# CameraMux4.net
KiCad netlist of a schematic drawn in EAGLE
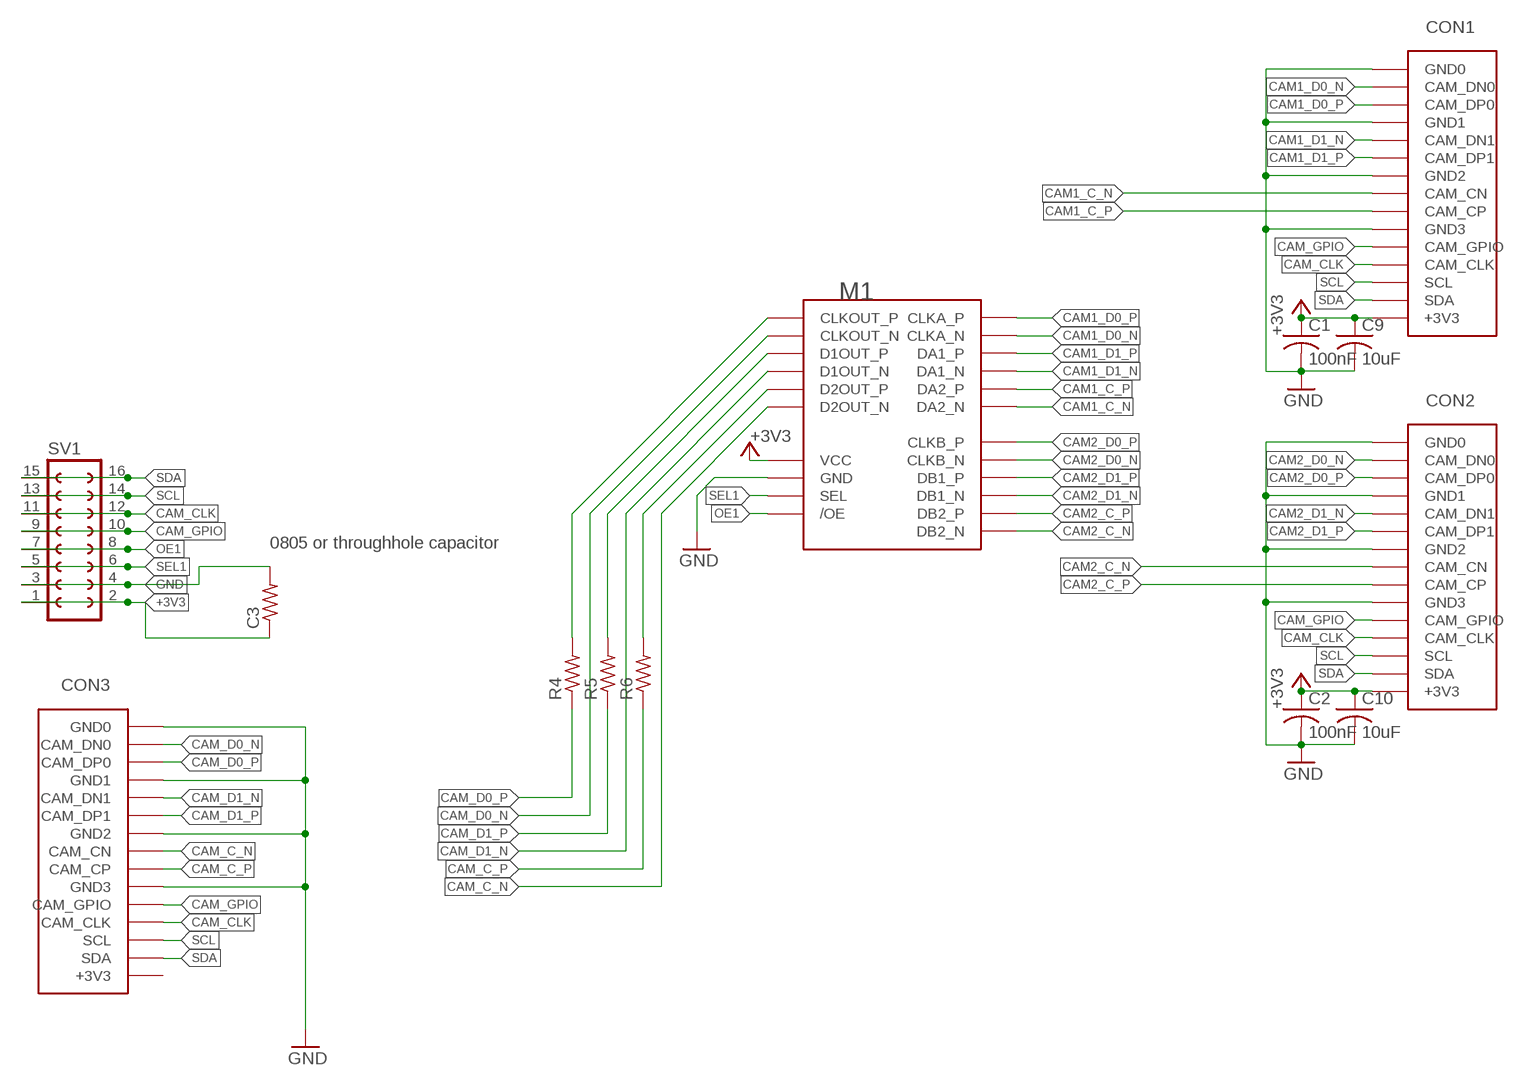
[diagram p0: schematic, sheet 1]

(export (version "E")
  (design (tool "Eeschema 10.0.6"))
  (components
    (comp (ref "C1")
      (value "100nF")
      (footprint "eagle-import:C0603")
      (libsource (lib "eagle-import") (part "C-USC0603"))
    )
    (comp (ref "C2")
      (value "100nF")
      (footprint "eagle-import:C0603")
      (libsource (lib "eagle-import") (part "C-USC0603"))
    )
    (comp (ref "C3")
      (value "R-US_FLIPFLOP")
      (footprint "eagle-import:0805-THM")
      (libsource (lib "eagle-import") (part "R-US_FLIPFLOP"))
    )
    (comp (ref "C9")
      (value "10uF")
      (footprint "eagle-import:C0603")
      (libsource (lib "eagle-import") (part "C-USC0603"))
    )
    (comp (ref "C10")
      (value "10uF")
      (footprint "eagle-import:C0603")
      (libsource (lib "eagle-import") (part "C-USC0603"))
    )
    (comp (ref "CON1")
      (value "XF3M(1)-1515-1B")
      (footprint "eagle-import:XF3M(1)-1515-1B")
      (libsource (lib "eagle-import") (part "XF3M(1)-1515-1B"))
    )
    (comp (ref "CON2")
      (value "XF3M(1)-1515-1B")
      (footprint "eagle-import:XF3M(1)-1515-1B")
      (libsource (lib "eagle-import") (part "XF3M(1)-1515-1B"))
    )
    (comp (ref "CON3")
      (value "XF3M(1)-1515-1B")
      (footprint "eagle-import:XF3M(1)-1515-1B")
      (libsource (lib "eagle-import") (part "XF3M(1)-1515-1B"))
    )
    (comp (ref "M1")
      (value "FSA642")
      (footprint "eagle-import:FSA642")
      (libsource (lib "eagle-import") (part "FSA642"))
    )
    (comp (ref "R4")
      (value "R-US_R0603")
      (footprint "eagle-import:R0603")
      (libsource (lib "eagle-import") (part "R-US_R0603"))
    )
    (comp (ref "R5")
      (value "R-US_R0603")
      (footprint "eagle-import:R0603")
      (libsource (lib "eagle-import") (part "R-US_R0603"))
    )
    (comp (ref "R6")
      (value "R-US_R0603")
      (footprint "eagle-import:R0603")
      (libsource (lib "eagle-import") (part "R-US_R0603"))
    )
    (comp (ref "SV1")
      (value "FE08-2")
      (footprint "eagle-import:FE08-2")
      (libsource (lib "eagle-import") (part "FE08-2"))
    )
  )
  (nets
    (net (code "1") (name "+3V3") (class "Default")
      (node (ref "C1") (pin "1") (pinfunction "1_1") (pintype "passive"))
      (node (ref "C10") (pin "1") (pinfunction "1_1") (pintype "passive"))
      (node (ref "C2") (pin "1") (pinfunction "1_1") (pintype "passive"))
      (node (ref "C3") (pin "1") (pinfunction "1_1") (pintype "passive"))
      (node (ref "C9") (pin "1") (pinfunction "1_1") (pintype "passive"))
      (node (ref "CON1") (pin "3V3") (pinfunction "+3V3_3V3") (pintype "bidirectional"))
      (node (ref "CON2") (pin "3V3") (pinfunction "+3V3_3V3") (pintype "bidirectional"))
      (node (ref "M1") (pin "VCC") (pinfunction "VCC_VCC") (pintype "bidirectional"))
      (node (ref "SV1") (pin "1") (pinfunction "1_1") (pintype "passive"))
      (node (ref "SV1") (pin "2") (pinfunction "2_2") (pintype "passive"))
    )
    (net (code "2") (name "CAM1_C_N") (class "Default")
      (node (ref "CON1") (pin "CAM_CN") (pinfunction "CAM_CN_CAM_CN") (pintype "bidirectional"))
      (node (ref "M1") (pin "DA2N") (pinfunction "DA2_N_DA2N") (pintype "bidirectional"))
    )
    (net (code "3") (name "CAM1_C_P") (class "Default")
      (node (ref "CON1") (pin "CAM_CP") (pinfunction "CAM_CP_CAM_CP") (pintype "bidirectional"))
      (node (ref "M1") (pin "DA2P") (pinfunction "DA2_P_DA2P") (pintype "bidirectional"))
    )
    (net (code "4") (name "CAM1_D0_N") (class "Default")
      (node (ref "CON1") (pin "CAM_DN0") (pinfunction "CAM_DN0_CAM_DN0") (pintype "bidirectional"))
      (node (ref "M1") (pin "CLKAN") (pinfunction "CLKA_N_CLKAN") (pintype "bidirectional"))
    )
    (net (code "5") (name "CAM1_D0_P") (class "Default")
      (node (ref "CON1") (pin "CAM_DP0") (pinfunction "CAM_DP0_CAM_DP0") (pintype "bidirectional"))
      (node (ref "M1") (pin "CLKAP") (pinfunction "CLKA_P_CLKAP") (pintype "bidirectional"))
    )
    (net (code "6") (name "CAM1_D1_N") (class "Default")
      (node (ref "CON1") (pin "CAM_DN1") (pinfunction "CAM_DN1_CAM_DN1") (pintype "bidirectional"))
      (node (ref "M1") (pin "DA1N") (pinfunction "DA1_N_DA1N") (pintype "bidirectional"))
    )
    (net (code "7") (name "CAM1_D1_P") (class "Default")
      (node (ref "CON1") (pin "CAM_DP1") (pinfunction "CAM_DP1_CAM_DP1") (pintype "bidirectional"))
      (node (ref "M1") (pin "DA1P") (pinfunction "DA1_P_DA1P") (pintype "bidirectional"))
    )
    (net (code "8") (name "CAM2_C_N") (class "Default")
      (node (ref "CON2") (pin "CAM_CN") (pinfunction "CAM_CN_CAM_CN") (pintype "bidirectional"))
      (node (ref "M1") (pin "DB2N") (pinfunction "DB2_N_DB2N") (pintype "bidirectional"))
    )
    (net (code "9") (name "CAM2_C_P") (class "Default")
      (node (ref "CON2") (pin "CAM_CP") (pinfunction "CAM_CP_CAM_CP") (pintype "bidirectional"))
      (node (ref "M1") (pin "DB2P") (pinfunction "DB2_P_DB2P") (pintype "bidirectional"))
    )
    (net (code "10") (name "CAM2_D0_N") (class "Default")
      (node (ref "CON2") (pin "CAM_DN0") (pinfunction "CAM_DN0_CAM_DN0") (pintype "bidirectional"))
      (node (ref "M1") (pin "CLKBN") (pinfunction "CLKB_N_CLKBN") (pintype "bidirectional"))
    )
    (net (code "11") (name "CAM2_D0_P") (class "Default")
      (node (ref "CON2") (pin "CAM_DP0") (pinfunction "CAM_DP0_CAM_DP0") (pintype "bidirectional"))
      (node (ref "M1") (pin "CLKBP") (pinfunction "CLKB_P_CLKBP") (pintype "bidirectional"))
    )
    (net (code "12") (name "CAM2_D1_N") (class "Default")
      (node (ref "CON2") (pin "CAM_DN1") (pinfunction "CAM_DN1_CAM_DN1") (pintype "bidirectional"))
      (node (ref "M1") (pin "DB1N") (pinfunction "DB1_N_DB1N") (pintype "bidirectional"))
    )
    (net (code "13") (name "CAM2_D1_P") (class "Default")
      (node (ref "CON2") (pin "CAM_DP1") (pinfunction "CAM_DP1_CAM_DP1") (pintype "bidirectional"))
      (node (ref "M1") (pin "DB1P") (pinfunction "DB1_P_DB1P") (pintype "bidirectional"))
    )
    (net (code "14") (name "CAM_CLK") (class "Default")
      (node (ref "CON1") (pin "CAM_CLK") (pinfunction "CAM_CLK_CAM_CLK") (pintype "bidirectional"))
      (node (ref "CON2") (pin "CAM_CLK") (pinfunction "CAM_CLK_CAM_CLK") (pintype "bidirectional"))
      (node (ref "CON3") (pin "CAM_CLK") (pinfunction "CAM_CLK_CAM_CLK") (pintype "bidirectional"))
      (node (ref "SV1") (pin "11") (pinfunction "11_11") (pintype "passive"))
      (node (ref "SV1") (pin "12") (pinfunction "12_12") (pintype "passive"))
    )
    (net (code "15") (name "CAM_C_N") (class "Default")
      (node (ref "CON3") (pin "CAM_CN") (pinfunction "CAM_CN_CAM_CN") (pintype "bidirectional"))
      (node (ref "M1") (pin "D2N") (pinfunction "D2OUT_N_D2N") (pintype "bidirectional"))
    )
    (net (code "16") (name "CAM_C_P") (class "Default")
      (node (ref "CON3") (pin "CAM_CP") (pinfunction "CAM_CP_CAM_CP") (pintype "bidirectional"))
      (node (ref "R6") (pin "1") (pinfunction "1_1") (pintype "passive"))
    )
    (net (code "17") (name "CAM_D0_N") (class "Default")
      (node (ref "CON3") (pin "CAM_DN0") (pinfunction "CAM_DN0_CAM_DN0") (pintype "bidirectional"))
      (node (ref "M1") (pin "CLKN") (pinfunction "CLKOUT_N_CLKN") (pintype "bidirectional"))
    )
    (net (code "18") (name "CAM_D0_P") (class "Default")
      (node (ref "CON3") (pin "CAM_DP0") (pinfunction "CAM_DP0_CAM_DP0") (pintype "bidirectional"))
      (node (ref "R4") (pin "1") (pinfunction "1_1") (pintype "passive"))
    )
    (net (code "19") (name "CAM_D1_N") (class "Default")
      (node (ref "CON3") (pin "CAM_DN1") (pinfunction "CAM_DN1_CAM_DN1") (pintype "bidirectional"))
      (node (ref "M1") (pin "D1N") (pinfunction "D1OUT_N_D1N") (pintype "bidirectional"))
    )
    (net (code "20") (name "CAM_D1_P") (class "Default")
      (node (ref "CON3") (pin "CAM_DP1") (pinfunction "CAM_DP1_CAM_DP1") (pintype "bidirectional"))
      (node (ref "R5") (pin "1") (pinfunction "1_1") (pintype "passive"))
    )
    (net (code "21") (name "CAM_GPIO") (class "Default")
      (node (ref "CON1") (pin "CAM_GPIO") (pinfunction "CAM_GPIO_CAM_GPIO") (pintype "bidirectional"))
      (node (ref "CON2") (pin "CAM_GPIO") (pinfunction "CAM_GPIO_CAM_GPIO") (pintype "bidirectional"))
      (node (ref "CON3") (pin "CAM_GPIO") (pinfunction "CAM_GPIO_CAM_GPIO") (pintype "bidirectional"))
      (node (ref "SV1") (pin "10") (pinfunction "10_10") (pintype "passive"))
      (node (ref "SV1") (pin "9") (pinfunction "9_9") (pintype "passive"))
    )
    (net (code "22") (name "GND") (class "Default")
      (node (ref "C1") (pin "2") (pinfunction "2_2") (pintype "passive"))
      (node (ref "C10") (pin "2") (pinfunction "2_2") (pintype "passive"))
      (node (ref "C2") (pin "2") (pinfunction "2_2") (pintype "passive"))
      (node (ref "C3") (pin "2") (pinfunction "2_2") (pintype "passive"))
      (node (ref "C9") (pin "2") (pinfunction "2_2") (pintype "passive"))
      (node (ref "CON1") (pin "GND0") (pinfunction "GND0_GND0") (pintype "bidirectional"))
      (node (ref "CON1") (pin "GND1") (pinfunction "GND1_GND1") (pintype "bidirectional"))
      (node (ref "CON1") (pin "GND2") (pinfunction "GND2_GND2") (pintype "bidirectional"))
      (node (ref "CON1") (pin "GND3") (pinfunction "GND3_GND3") (pintype "bidirectional"))
      (node (ref "CON2") (pin "GND0") (pinfunction "GND0_GND0") (pintype "bidirectional"))
      (node (ref "CON2") (pin "GND1") (pinfunction "GND1_GND1") (pintype "bidirectional"))
      (node (ref "CON2") (pin "GND2") (pinfunction "GND2_GND2") (pintype "bidirectional"))
      (node (ref "CON2") (pin "GND3") (pinfunction "GND3_GND3") (pintype "bidirectional"))
      (node (ref "CON3") (pin "GND0") (pinfunction "GND0_GND0") (pintype "bidirectional"))
      (node (ref "CON3") (pin "GND1") (pinfunction "GND1_GND1") (pintype "bidirectional"))
      (node (ref "CON3") (pin "GND2") (pinfunction "GND2_GND2") (pintype "bidirectional"))
      (node (ref "CON3") (pin "GND3") (pinfunction "GND3_GND3") (pintype "bidirectional"))
      (node (ref "M1") (pin "GND") (pinfunction "GND_GND") (pintype "bidirectional"))
      (node (ref "SV1") (pin "3") (pinfunction "3_3") (pintype "passive"))
      (node (ref "SV1") (pin "4") (pinfunction "4_4") (pintype "passive"))
    )
    (net (code "23") (name "Net-(M1-CLKOUT_P)") (class "Default")
      (node (ref "M1") (pin "CLKP") (pinfunction "CLKOUT_P_CLKP") (pintype "bidirectional"))
      (node (ref "R4") (pin "2") (pinfunction "2_2") (pintype "passive"))
    )
    (net (code "24") (name "Net-(M1-D1OUT_P)") (class "Default")
      (node (ref "M1") (pin "D1P") (pinfunction "D1OUT_P_D1P") (pintype "bidirectional"))
      (node (ref "R5") (pin "2") (pinfunction "2_2") (pintype "passive"))
    )
    (net (code "25") (name "Net-(M1-D2OUT_P)") (class "Default")
      (node (ref "M1") (pin "D2P") (pinfunction "D2OUT_P_D2P") (pintype "bidirectional"))
      (node (ref "R6") (pin "2") (pinfunction "2_2") (pintype "passive"))
    )
    (net (code "26") (name "OE1") (class "Default")
      (node (ref "M1") (pin "/OE") (pinfunction "/OE_/OE") (pintype "bidirectional"))
      (node (ref "SV1") (pin "7") (pinfunction "7_7") (pintype "passive"))
      (node (ref "SV1") (pin "8") (pinfunction "8_8") (pintype "passive"))
    )
    (net (code "27") (name "SCL") (class "Default")
      (node (ref "CON1") (pin "SCL") (pinfunction "SCL_SCL") (pintype "bidirectional"))
      (node (ref "CON2") (pin "SCL") (pinfunction "SCL_SCL") (pintype "bidirectional"))
      (node (ref "CON3") (pin "SCL") (pinfunction "SCL_SCL") (pintype "bidirectional"))
      (node (ref "SV1") (pin "13") (pinfunction "13_13") (pintype "passive"))
      (node (ref "SV1") (pin "14") (pinfunction "14_14") (pintype "passive"))
    )
    (net (code "28") (name "SDA") (class "Default")
      (node (ref "CON1") (pin "SDA") (pinfunction "SDA_SDA") (pintype "bidirectional"))
      (node (ref "CON2") (pin "SDA") (pinfunction "SDA_SDA") (pintype "bidirectional"))
      (node (ref "CON3") (pin "SDA") (pinfunction "SDA_SDA") (pintype "bidirectional"))
      (node (ref "SV1") (pin "15") (pinfunction "15_15") (pintype "passive"))
      (node (ref "SV1") (pin "16") (pinfunction "16_16") (pintype "passive"))
    )
    (net (code "29") (name "SEL1") (class "Default")
      (node (ref "M1") (pin "SEL") (pinfunction "SEL_SEL") (pintype "bidirectional"))
      (node (ref "SV1") (pin "5") (pinfunction "5_5") (pintype "passive"))
      (node (ref "SV1") (pin "6") (pinfunction "6_6") (pintype "passive"))
    )
    (net (code "30") (name "unconnected-(CON3-+3V3-Pad3V3)") (class "Default")
      (node (ref "CON3") (pin "3V3") (pinfunction "+3V3_3V3") (pintype "bidirectional"))
    )
  )
)
